# buttonBoard.net
KiCad netlist of a schematic drawn in EAGLE
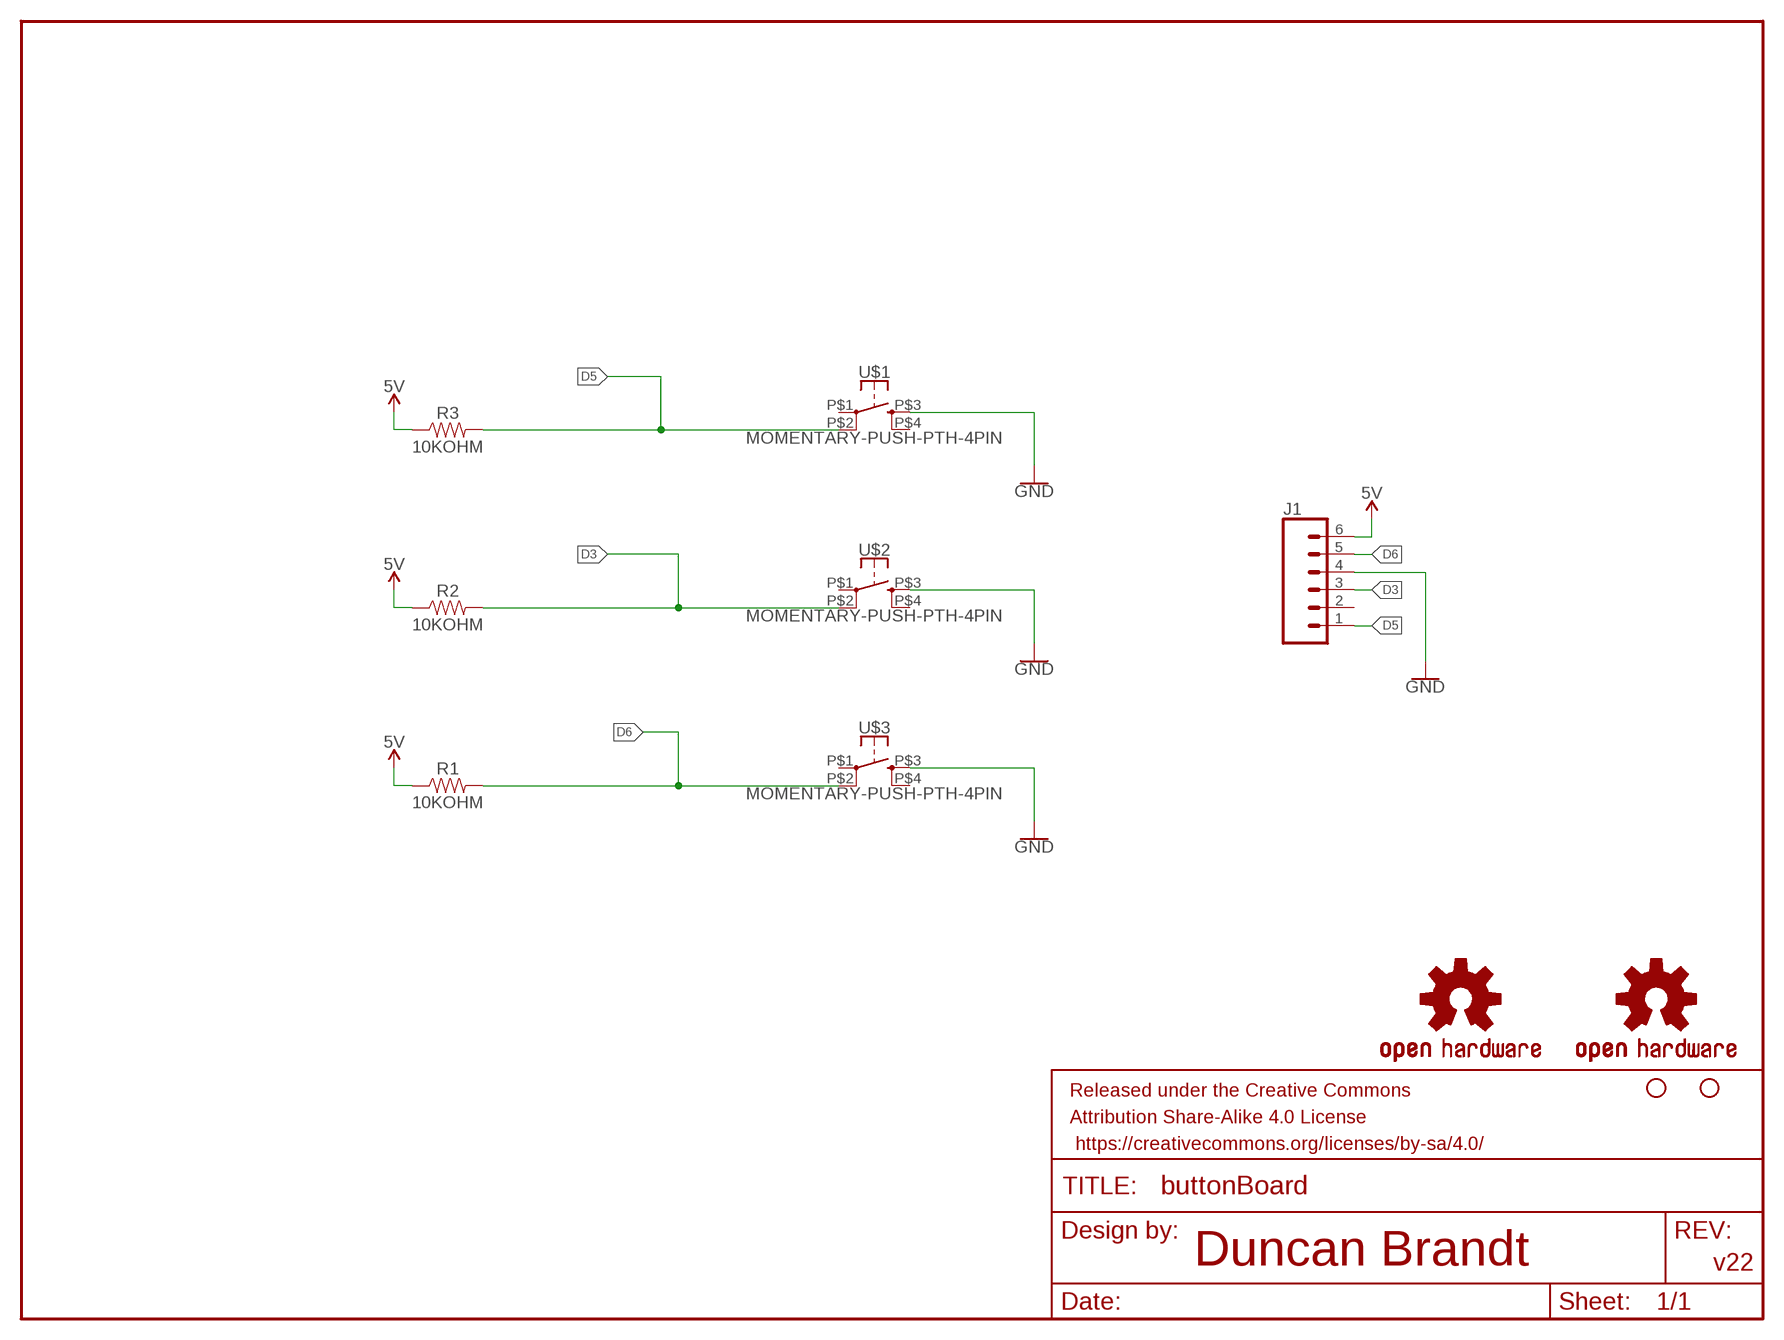
[diagram p0: schematic, sheet 1]

(export (version "E")
  (design (tool "Eeschema 10.0.6"))
  (components
    (comp (ref "FRAME2")
      (value "FRAME-LETTER")
      (footprint "eagle-import:CREATIVE_COMMONS")
      (libsource (lib "eagle-import") (part "FRAME-LETTER"))
    )
    (comp (ref "J1")
      (value "CONN_06SILK_FEMALE_PTH")
      (footprint "eagle-import:1X06")
      (libsource (lib "eagle-import") (part "CONN_06SILK_FEMALE_PTH"))
    )
    (comp (ref "JP3")
      (value "STAND-OFF")
      (footprint "eagle-import:STAND-OFF")
      (libsource (lib "eagle-import") (part "STAND-OFF"))
    )
    (comp (ref "JP6")
      (value "STAND-OFF")
      (footprint "eagle-import:STAND-OFF")
      (libsource (lib "eagle-import") (part "STAND-OFF"))
    )
    (comp (ref "R1")
      (value "10KOHM")
      (footprint "eagle-import:AXIAL-0.3")
      (libsource (lib "eagle-import") (part "10KOHM"))
    )
    (comp (ref "R2")
      (value "10KOHM")
      (footprint "eagle-import:AXIAL-0.3")
      (libsource (lib "eagle-import") (part "10KOHM"))
    )
    (comp (ref "R3")
      (value "10KOHM")
      (footprint "eagle-import:AXIAL-0.3")
      (libsource (lib "eagle-import") (part "10KOHM"))
    )
    (comp (ref "U$1")
      (value "MOMENTARY-PUSH-PTH-4PIN")
      (footprint "eagle-import:SOFTPUSH_BTN_PTH_0.2INCH")
      (libsource (lib "eagle-import") (part "MOMENTARY-PUSH-PTH-4PIN"))
    )
    (comp (ref "U$2")
      (value "MOMENTARY-PUSH-PTH-4PIN")
      (footprint "eagle-import:SOFTPUSH_BTN_PTH_0.2INCH")
      (libsource (lib "eagle-import") (part "MOMENTARY-PUSH-PTH-4PIN"))
    )
    (comp (ref "U$3")
      (value "MOMENTARY-PUSH-PTH-4PIN")
      (footprint "eagle-import:SOFTPUSH_BTN_PTH_0.2INCH")
      (libsource (lib "eagle-import") (part "MOMENTARY-PUSH-PTH-4PIN"))
    )
    (comp (ref "U$4")
      (value "OSHW-LOGOS")
      (footprint "eagle-import:OSHW-LOGO-S")
      (libsource (lib "eagle-import") (part "OSHW-LOGOS"))
    )
    (comp (ref "U$16")
      (value "OSHW-LOGOS")
      (footprint "eagle-import:OSHW-LOGO-S")
      (libsource (lib "eagle-import") (part "OSHW-LOGOS"))
    )
  )
  (nets
    (net (code "1") (name "5V") (class "Default")
      (node (ref "J1") (pin "6") (pinfunction "6_6") (pintype "passive"))
      (node (ref "R1") (pin "P$1") (pinfunction "1_P$1") (pintype "passive"))
      (node (ref "R2") (pin "P$1") (pinfunction "1_P$1") (pintype "passive"))
      (node (ref "R3") (pin "P$1") (pinfunction "1_P$1") (pintype "passive"))
    )
    (net (code "2") (name "D3") (class "Default")
      (node (ref "J1") (pin "3") (pinfunction "3_3") (pintype "passive"))
      (node (ref "R2") (pin "P$2") (pinfunction "2_P$2") (pintype "passive"))
      (node (ref "U$2") (pin "P$2") (pinfunction "2_P$2") (pintype "passive"))
    )
    (net (code "3") (name "D5") (class "Default")
      (node (ref "J1") (pin "1") (pinfunction "1_1") (pintype "passive"))
      (node (ref "R3") (pin "P$2") (pinfunction "2_P$2") (pintype "passive"))
      (node (ref "U$1") (pin "P$2") (pinfunction "2_P$2") (pintype "passive"))
    )
    (net (code "4") (name "D6") (class "Default")
      (node (ref "J1") (pin "5") (pinfunction "5_5") (pintype "passive"))
      (node (ref "R1") (pin "P$2") (pinfunction "2_P$2") (pintype "passive"))
      (node (ref "U$3") (pin "P$2") (pinfunction "2_P$2") (pintype "passive"))
    )
    (net (code "5") (name "GND") (class "Default")
      (node (ref "J1") (pin "4") (pinfunction "4_4") (pintype "passive"))
      (node (ref "U$1") (pin "P$3") (pinfunction "3_P$3") (pintype "passive"))
      (node (ref "U$2") (pin "P$3") (pinfunction "3_P$3") (pintype "passive"))
      (node (ref "U$3") (pin "P$3") (pinfunction "3_P$3") (pintype "passive"))
    )
    (net (code "6") (name "unconnected-(J1-Pad2)") (class "Default")
      (node (ref "J1") (pin "2") (pinfunction "2_2") (pintype "passive"))
    )
    (net (code "7") (name "unconnected-(U$1-1-PadP$1)") (class "Default")
      (node (ref "U$1") (pin "P$1") (pinfunction "1_P$1") (pintype "passive"))
    )
    (net (code "8") (name "unconnected-(U$1-4-PadP$4)") (class "Default")
      (node (ref "U$1") (pin "P$4") (pinfunction "4_P$4") (pintype "passive"))
    )
    (net (code "9") (name "unconnected-(U$2-1-PadP$1)") (class "Default")
      (node (ref "U$2") (pin "P$1") (pinfunction "1_P$1") (pintype "passive"))
    )
    (net (code "10") (name "unconnected-(U$2-4-PadP$4)") (class "Default")
      (node (ref "U$2") (pin "P$4") (pinfunction "4_P$4") (pintype "passive"))
    )
    (net (code "11") (name "unconnected-(U$3-1-PadP$1)") (class "Default")
      (node (ref "U$3") (pin "P$1") (pinfunction "1_P$1") (pintype "passive"))
    )
    (net (code "12") (name "unconnected-(U$3-4-PadP$4)") (class "Default")
      (node (ref "U$3") (pin "P$4") (pinfunction "4_P$4") (pintype "passive"))
    )
  )
)
